# SolenoidDrive.net
KiCad netlist of a schematic drawn in Altium Designer
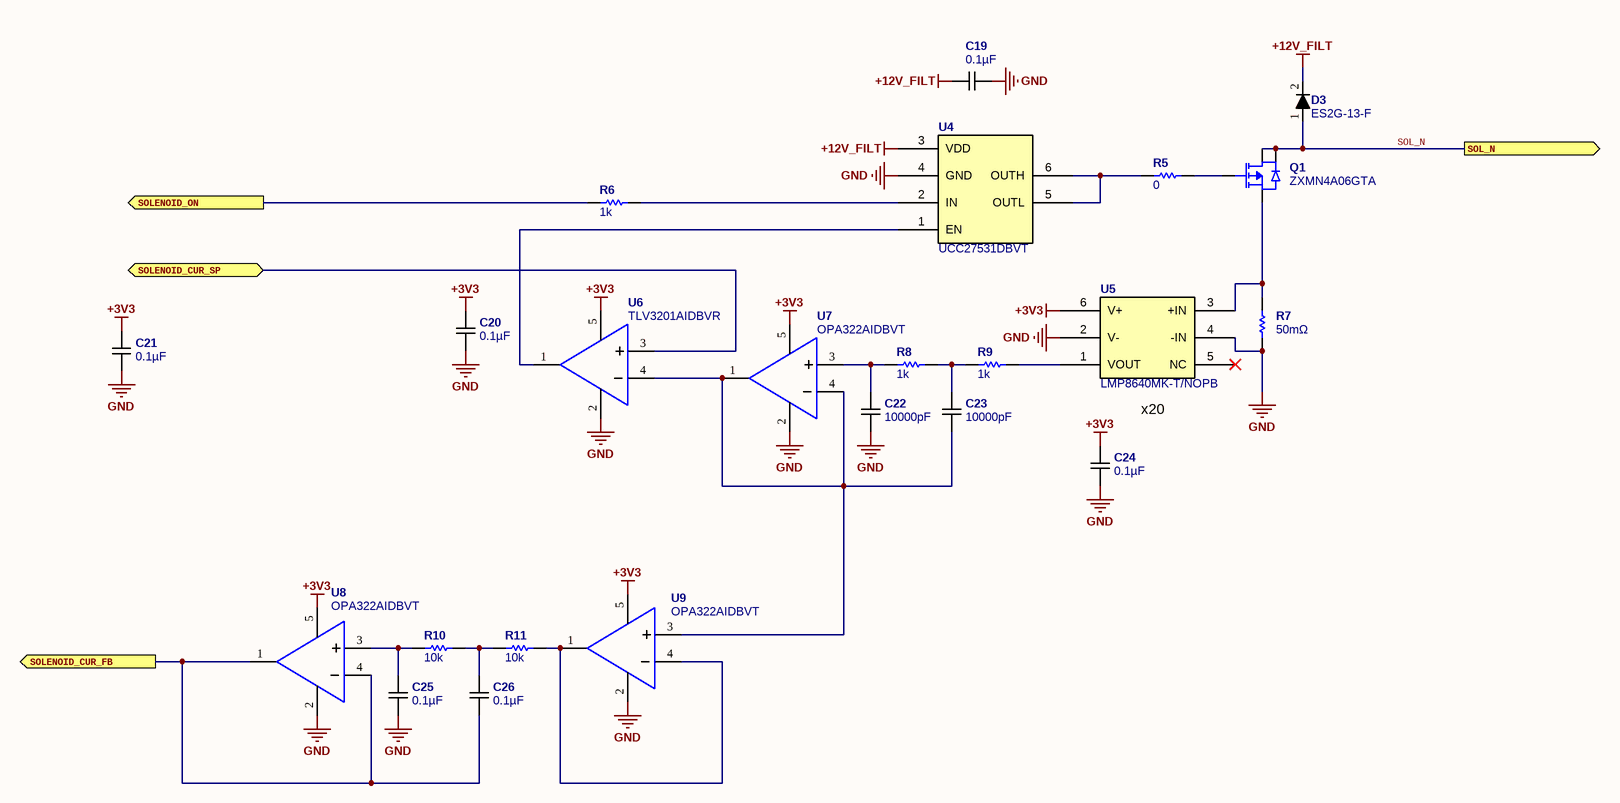
[diagram p0: SolenoidDrive.SchDoc]

(export (version "E")
  (design (tool "Eeschema 10.0.6"))
  (components
    (comp (ref "C19")
      (value "0.1µF")
      (footprint "C0402_0.55MM_HD")
      (description "CAP CER 0.1UF 25V X7R 0402")
      (fields
        (field (name "MANUFACTURER PART NUMBER") "CGA2B3X7R1E104K050BB")
        (field (name "MANUFACTURER") "TDK Corporation")
      )
      (libsource (lib "Capacitors - TDK- AEC-Q200") (part "C_2P_NP"))
    )
    (comp (ref "C20")
      (value "0.1µF")
      (footprint "C0402_0.55MM_HD")
      (description "CAP CER 0.1UF 25V X7R 0402")
      (fields
        (field (name "MANUFACTURER PART NUMBER") "CGA2B3X7R1E104K050BB")
        (field (name "MANUFACTURER") "TDK Corporation")
      )
      (libsource (lib "Capacitors - TDK- AEC-Q200") (part "C_2P_NP"))
    )
    (comp (ref "C21")
      (value "0.1µF")
      (footprint "C0402_0.55MM_HD")
      (description "CAP CER 0.1UF 25V X7R 0402")
      (fields
        (field (name "MANUFACTURER PART NUMBER") "CGA2B3X7R1E104K050BB")
        (field (name "MANUFACTURER") "TDK Corporation")
      )
      (libsource (lib "Capacitors - TDK- AEC-Q200") (part "C_2P_NP"))
    )
    (comp (ref "C22")
      (value "10000pF")
      (footprint "C0603_0.90MM_HD")
      (description "CAP CER 10000PF 50V C0G 0603")
      (fields
        (field (name "MANUFACTURER PART NUMBER") "CGA3E2C0G1H103J080AA")
        (field (name "MANUFACTURER") "TDK Corporation")
      )
      (libsource (lib "Capacitors - TDK- AEC-Q200") (part "C_2P_NP"))
    )
    (comp (ref "C23")
      (value "10000pF")
      (footprint "C0603_0.90MM_HD")
      (description "CAP CER 10000PF 50V C0G 0603")
      (fields
        (field (name "MANUFACTURER PART NUMBER") "CGA3E2C0G1H103J080AA")
        (field (name "MANUFACTURER") "TDK Corporation")
      )
      (libsource (lib "Capacitors - TDK- AEC-Q200") (part "C_2P_NP"))
    )
    (comp (ref "C24")
      (value "0.1µF")
      (footprint "C0402_0.55MM_HD")
      (description "CAP CER 0.1UF 25V X7R 0402")
      (fields
        (field (name "MANUFACTURER PART NUMBER") "CGA2B3X7R1E104K050BB")
        (field (name "MANUFACTURER") "TDK Corporation")
      )
      (libsource (lib "Capacitors - TDK- AEC-Q200") (part "C_2P_NP"))
    )
    (comp (ref "C25")
      (value "0.1µF")
      (footprint "C0402_0.55MM_HD")
      (description "CAP CER 0.1UF 25V X7R 0402")
      (fields
        (field (name "MANUFACTURER PART NUMBER") "CGA2B3X7R1E104K050BB")
        (field (name "MANUFACTURER") "TDK Corporation")
      )
      (libsource (lib "Capacitors - TDK- AEC-Q200") (part "C_2P_NP"))
    )
    (comp (ref "C26")
      (value "0.1µF")
      (footprint "C0402_0.55MM_HD")
      (description "CAP CER 0.1UF 25V X7R 0402")
      (fields
        (field (name "MANUFACTURER PART NUMBER") "CGA2B3X7R1E104K050BB")
        (field (name "MANUFACTURER") "TDK Corporation")
      )
      (libsource (lib "Capacitors - TDK- AEC-Q200") (part "C_2P_NP"))
    )
    (comp (ref "D3")
      (value "ES2G-13-F")
      (footprint "D_SMB_P")
      (description "DIODE SUPER FAST 2A 400V SMB")
      (fields (field (name "MANUFACTURER") "Diodes Inc"))
      (libsource (lib "Diodes") (part "DP_1A_2C"))
    )
    (comp (ref "Q1")
      (value "ZXMN4A06GTA")
      (footprint "SOT223")
      (description "Trans MOSFET N-CH 40V 7A 4-Pin(3+Tab) SOT-223 T/R")
      (fields (field (name "MANUFACTURER") "Diodes Zetex"))
      (libsource (lib "eTransistor") (part "ZXMN4A06GTA"))
    )
    (comp (ref "R5")
      (value "0")
      (footprint "R0603_0.55MM_MD")
      (description "RES 0.0 OHM 1/10W JUMP 0603 SMD")
      (fields
        (field (name "MANUFACTURER PART NUMBER") "ERJ-3GEY0R00V")
        (field (name "MANUFACTURER") "Panasonic Electronic Components")
      )
      (libsource (lib "Resistors - Panasonic - AEC-Q200") (part "R_2P"))
    )
    (comp (ref "R6")
      (value "1k")
      (footprint "R0603_0.55MM_MD")
      (description "RES 1K OHM 1/10W 1% 0603 SMD")
      (fields
        (field (name "MANUFACTURER PART NUMBER") "ERJ-3EKF1001V")
        (field (name "MANUFACTURER") "Panasonic Electronic Components")
      )
      (libsource (lib "Resistors - Panasonic - AEC-Q200") (part "R_2P"))
    )
    (comp (ref "R7")
      (value "50mΩ")
      (footprint "R1206_0.60MM_HD")
      (description "RES 0.05 OHM 1% 1/2W 1206")
      (fields
        (field (name "MANUFACTURER") "KOA Speer Electronics, Inc.")
        (field (name "MANUFACTURER PART NUMBER") "UR73V2BTTD50L0F")
      )
      (libsource (lib "Resistors - KOA Speer -Current Sense - AEC-Q200") (part "R_2P"))
    )
    (comp (ref "R8")
      (value "1k")
      (footprint "R0603_0.55MM_MD")
      (description "RES 1K OHM 1/10W 1% 0603 SMD")
      (fields
        (field (name "MANUFACTURER PART NUMBER") "ERJ-3EKF1001V")
        (field (name "MANUFACTURER") "Panasonic Electronic Components")
      )
      (libsource (lib "Resistors - Panasonic - AEC-Q200") (part "R_2P"))
    )
    (comp (ref "R9")
      (value "1k")
      (footprint "R0603_0.55MM_MD")
      (description "RES 1K OHM 1/10W 1% 0603 SMD")
      (fields
        (field (name "MANUFACTURER PART NUMBER") "ERJ-3EKF1001V")
        (field (name "MANUFACTURER") "Panasonic Electronic Components")
      )
      (libsource (lib "Resistors - Panasonic - AEC-Q200") (part "R_2P"))
    )
    (comp (ref "R10")
      (value "10k")
      (footprint "R0603_0.55MM_MD")
      (description "RES 10K OHM 1/10W 1% 0603 SMD")
      (fields
        (field (name "MANUFACTURER PART NUMBER") "ERJ-3EKF1002V")
        (field (name "MANUFACTURER") "Panasonic Electronic Components")
      )
      (libsource (lib "Resistors - Panasonic - AEC-Q200") (part "R_2P"))
    )
    (comp (ref "R11")
      (value "10k")
      (footprint "R0603_0.55MM_MD")
      (description "RES 10K OHM 1/10W 1% 0603 SMD")
      (fields
        (field (name "MANUFACTURER PART NUMBER") "ERJ-3EKF1002V")
        (field (name "MANUFACTURER") "Panasonic Electronic Components")
      )
      (libsource (lib "Resistors - Panasonic - AEC-Q200") (part "R_2P"))
    )
    (comp (ref "U4")
      (value "UCC27531DBVT")
      (footprint "SOT95P245X145-6L")
      (description "IC GATE DRVR IGBT/MOSFET SOT23-6")
      (fields (field (name "MANUFACTURER") "Texas Instruments"))
      (libsource (lib "eIC") (part "UCC27531DBVT"))
    )
    (comp (ref "U5")
      (value "LMP8640MK-T/NOPB")
      (footprint "SOT95P245X145-6L")
      (description "IC OPAMP CURR SENSE 6SOT")
      (fields (field (name "MANUFACTURER") "TI National Semiconductor"))
      (libsource (lib "eIC") (part "LMP8640MK-T/NOPB"))
    )
    (comp (ref "U6")
      (value "TLV3201AIDBVR")
      (footprint "SOT23-5")
      (description "Single high speed, low power comparator 5-SOT-23 -40 to 125")
      (fields (field (name "MANUFACTURER") "Texas Instruments"))
      (libsource (lib "eOPAMP") (part "TLV3201AIDBVR"))
    )
    (comp (ref "U7")
      (value "OPA322AIDBVT")
      (footprint "SOT23-5")
      (description "IC OPAMP GP 20MHZ RRO SOT23-5")
      (fields (field (name "MANUFACTURER") "Texas Instruments"))
      (libsource (lib "eOPAMP") (part "OPA322AIDBVT"))
    )
    (comp (ref "U8")
      (value "OPA322AIDBVT")
      (footprint "SOT23-5")
      (description "IC OPAMP GP 20MHZ RRO SOT23-5")
      (fields (field (name "MANUFACTURER") "Texas Instruments"))
      (libsource (lib "eOPAMP") (part "OPA322AIDBVT"))
    )
    (comp (ref "U9")
      (value "OPA322AIDBVT")
      (footprint "SOT23-5")
      (description "IC OPAMP GP 20MHZ RRO SOT23-5")
      (fields (field (name "MANUFACTURER") "Texas Instruments"))
      (libsource (lib "eOPAMP") (part "OPA322AIDBVT"))
    )
  )
  (nets
    (net (code "1") (name "+3V3") (class "Default")
      (node (ref "C20") (pin "1") (pinfunction "1_1") (pintype "passive"))
      (node (ref "C21") (pin "1") (pinfunction "1_1") (pintype "passive"))
      (node (ref "C24") (pin "1") (pinfunction "1_1") (pintype "passive"))
      (node (ref "U5") (pin "6") (pinfunction "V+_6") (pintype "passive"))
      (node (ref "U6") (pin "5") (pinfunction "VCC_5") (pintype "passive"))
      (node (ref "U7") (pin "5") (pinfunction "VCC_5") (pintype "passive"))
      (node (ref "U8") (pin "5") (pinfunction "VCC_5") (pintype "passive"))
      (node (ref "U9") (pin "5") (pinfunction "VCC_5") (pintype "passive"))
    )
    (net (code "2") (name "+12V_FILT") (class "Default")
      (node (ref "C19") (pin "1") (pinfunction "1_1") (pintype "passive"))
      (node (ref "D3") (pin "2") (pinfunction "K_2") (pintype "passive"))
      (node (ref "U4") (pin "3") (pinfunction "VDD_3") (pintype "passive"))
    )
    (net (code "3") (name "/SOLENOID_CUR_FB") (class "Default")
      (node (ref "C26") (pin "2") (pinfunction "1_2") (pintype "passive"))
      (node (ref "U8") (pin "1") (pinfunction "OUT_1") (pintype "passive"))
      (node (ref "U8") (pin "4") (pinfunction "-_4") (pintype "passive"))
    )
    (net (code "4") (name "/SOLENOID_CUR_SP") (class "Default")
      (node (ref "U6") (pin "3") (pinfunction "+_3") (pintype "passive"))
    )
    (net (code "5") (name "/SOLENOID_ON") (class "Default")
      (node (ref "R6") (pin "1") (pinfunction "1_1") (pintype "passive"))
    )
    (net (code "6") (name "/SOL_N") (class "Default")
      (node (ref "D3") (pin "1") (pinfunction "A_1") (pintype "passive"))
      (node (ref "Q1") (pin "2") (pinfunction "D_2") (pintype "passive"))
      (node (ref "Q1") (pin "4") (pinfunction "D_4") (pintype "passive"))
    )
    (net (code "7") (name "GND") (class "Default")
      (node (ref "C19") (pin "2") (pinfunction "1_2") (pintype "passive"))
      (node (ref "C20") (pin "2") (pinfunction "1_2") (pintype "passive"))
      (node (ref "C21") (pin "2") (pinfunction "1_2") (pintype "passive"))
      (node (ref "C22") (pin "1") (pinfunction "1_1") (pintype "passive"))
      (node (ref "C24") (pin "2") (pinfunction "1_2") (pintype "passive"))
      (node (ref "C25") (pin "2") (pinfunction "1_2") (pintype "passive"))
      (node (ref "R7") (pin "1") (pinfunction "1_1") (pintype "passive"))
      (node (ref "U4") (pin "4") (pinfunction "GND_4") (pintype "passive"))
      (node (ref "U5") (pin "2") (pinfunction "V-_2") (pintype "passive"))
      (node (ref "U5") (pin "4") (pinfunction "-IN_4") (pintype "passive"))
      (node (ref "U6") (pin "2") (pinfunction "GND_2") (pintype "passive"))
      (node (ref "U7") (pin "2") (pinfunction "GND_2") (pintype "passive"))
      (node (ref "U8") (pin "2") (pinfunction "GND_2") (pintype "passive"))
      (node (ref "U9") (pin "2") (pinfunction "GND_2") (pintype "passive"))
    )
    (net (code "8") (name "Net-(C23-1-Pad2)") (class "Default")
      (node (ref "C23") (pin "2") (pinfunction "1_2") (pintype "passive"))
      (node (ref "R8") (pin "1") (pinfunction "1_1") (pintype "passive"))
      (node (ref "R9") (pin "2") (pinfunction "2_2") (pintype "passive"))
    )
    (net (code "9") (name "Net-(C26-Pad1)") (class "Default")
      (node (ref "C26") (pin "1") (pinfunction "1_1") (pintype "passive"))
      (node (ref "R10") (pin "1") (pinfunction "1_1") (pintype "passive"))
      (node (ref "R11") (pin "2") (pinfunction "2_2") (pintype "passive"))
    )
    (net (code "10") (name "Net-(Q1-G)") (class "Default")
      (node (ref "Q1") (pin "1") (pinfunction "G_1") (pintype "passive"))
      (node (ref "R5") (pin "1") (pinfunction "1_1") (pintype "passive"))
    )
    (net (code "11") (name "Net-(Q1-S)") (class "Default")
      (node (ref "Q1") (pin "3") (pinfunction "S_3") (pintype "passive"))
      (node (ref "R7") (pin "2") (pinfunction "2_2") (pintype "passive"))
      (node (ref "U5") (pin "3") (pinfunction "+IN_3") (pintype "passive"))
    )
    (net (code "12") (name "Net-(U4-EN)") (class "Default")
      (node (ref "U4") (pin "1") (pinfunction "EN_1") (pintype "passive"))
      (node (ref "U6") (pin "1") (pinfunction "OUT_1") (pintype "passive"))
    )
    (net (code "13") (name "Net-(U4-IN)") (class "Default")
      (node (ref "R6") (pin "2") (pinfunction "2_2") (pintype "passive"))
      (node (ref "U4") (pin "2") (pinfunction "IN_2") (pintype "passive"))
    )
    (net (code "14") (name "Net-(U4-OUTH)") (class "Default")
      (node (ref "R5") (pin "2") (pinfunction "2_2") (pintype "passive"))
      (node (ref "U4") (pin "5") (pinfunction "OUTL_5") (pintype "passive"))
      (node (ref "U4") (pin "6") (pinfunction "OUTH_6") (pintype "passive"))
    )
    (net (code "15") (name "Net-(U5-VOUT)") (class "Default")
      (node (ref "R9") (pin "1") (pinfunction "1_1") (pintype "passive"))
      (node (ref "U5") (pin "1") (pinfunction "VOUT_1") (pintype "passive"))
    )
    (net (code "16") (name "Net-(U6--)") (class "Default")
      (node (ref "C23") (pin "1") (pinfunction "1_1") (pintype "passive"))
      (node (ref "U6") (pin "4") (pinfunction "-_4") (pintype "passive"))
      (node (ref "U7") (pin "1") (pinfunction "OUT_1") (pintype "passive"))
      (node (ref "U7") (pin "4") (pinfunction "-_4") (pintype "passive"))
      (node (ref "U9") (pin "3") (pinfunction "+_3") (pintype "passive"))
    )
    (net (code "17") (name "Net-(U7-+)") (class "Default")
      (node (ref "C22") (pin "2") (pinfunction "1_2") (pintype "passive"))
      (node (ref "R8") (pin "2") (pinfunction "2_2") (pintype "passive"))
      (node (ref "U7") (pin "3") (pinfunction "+_3") (pintype "passive"))
    )
    (net (code "18") (name "Net-(U8-+)") (class "Default")
      (node (ref "C25") (pin "1") (pinfunction "1_1") (pintype "passive"))
      (node (ref "R10") (pin "2") (pinfunction "2_2") (pintype "passive"))
      (node (ref "U8") (pin "3") (pinfunction "+_3") (pintype "passive"))
    )
    (net (code "19") (name "Net-(U9--)") (class "Default")
      (node (ref "R11") (pin "1") (pinfunction "1_1") (pintype "passive"))
      (node (ref "U9") (pin "1") (pinfunction "OUT_1") (pintype "passive"))
      (node (ref "U9") (pin "4") (pinfunction "-_4") (pintype "passive"))
    )
    (net (code "20") (name "unconnected-(U5-NC-Pad5)") (class "Default")
      (node (ref "U5") (pin "5") (pinfunction "NC_5") (pintype "passive+no_connect"))
    )
  )
)
